# NextPro-v1.net
KiCad netlist of a schematic drawn in EAGLE
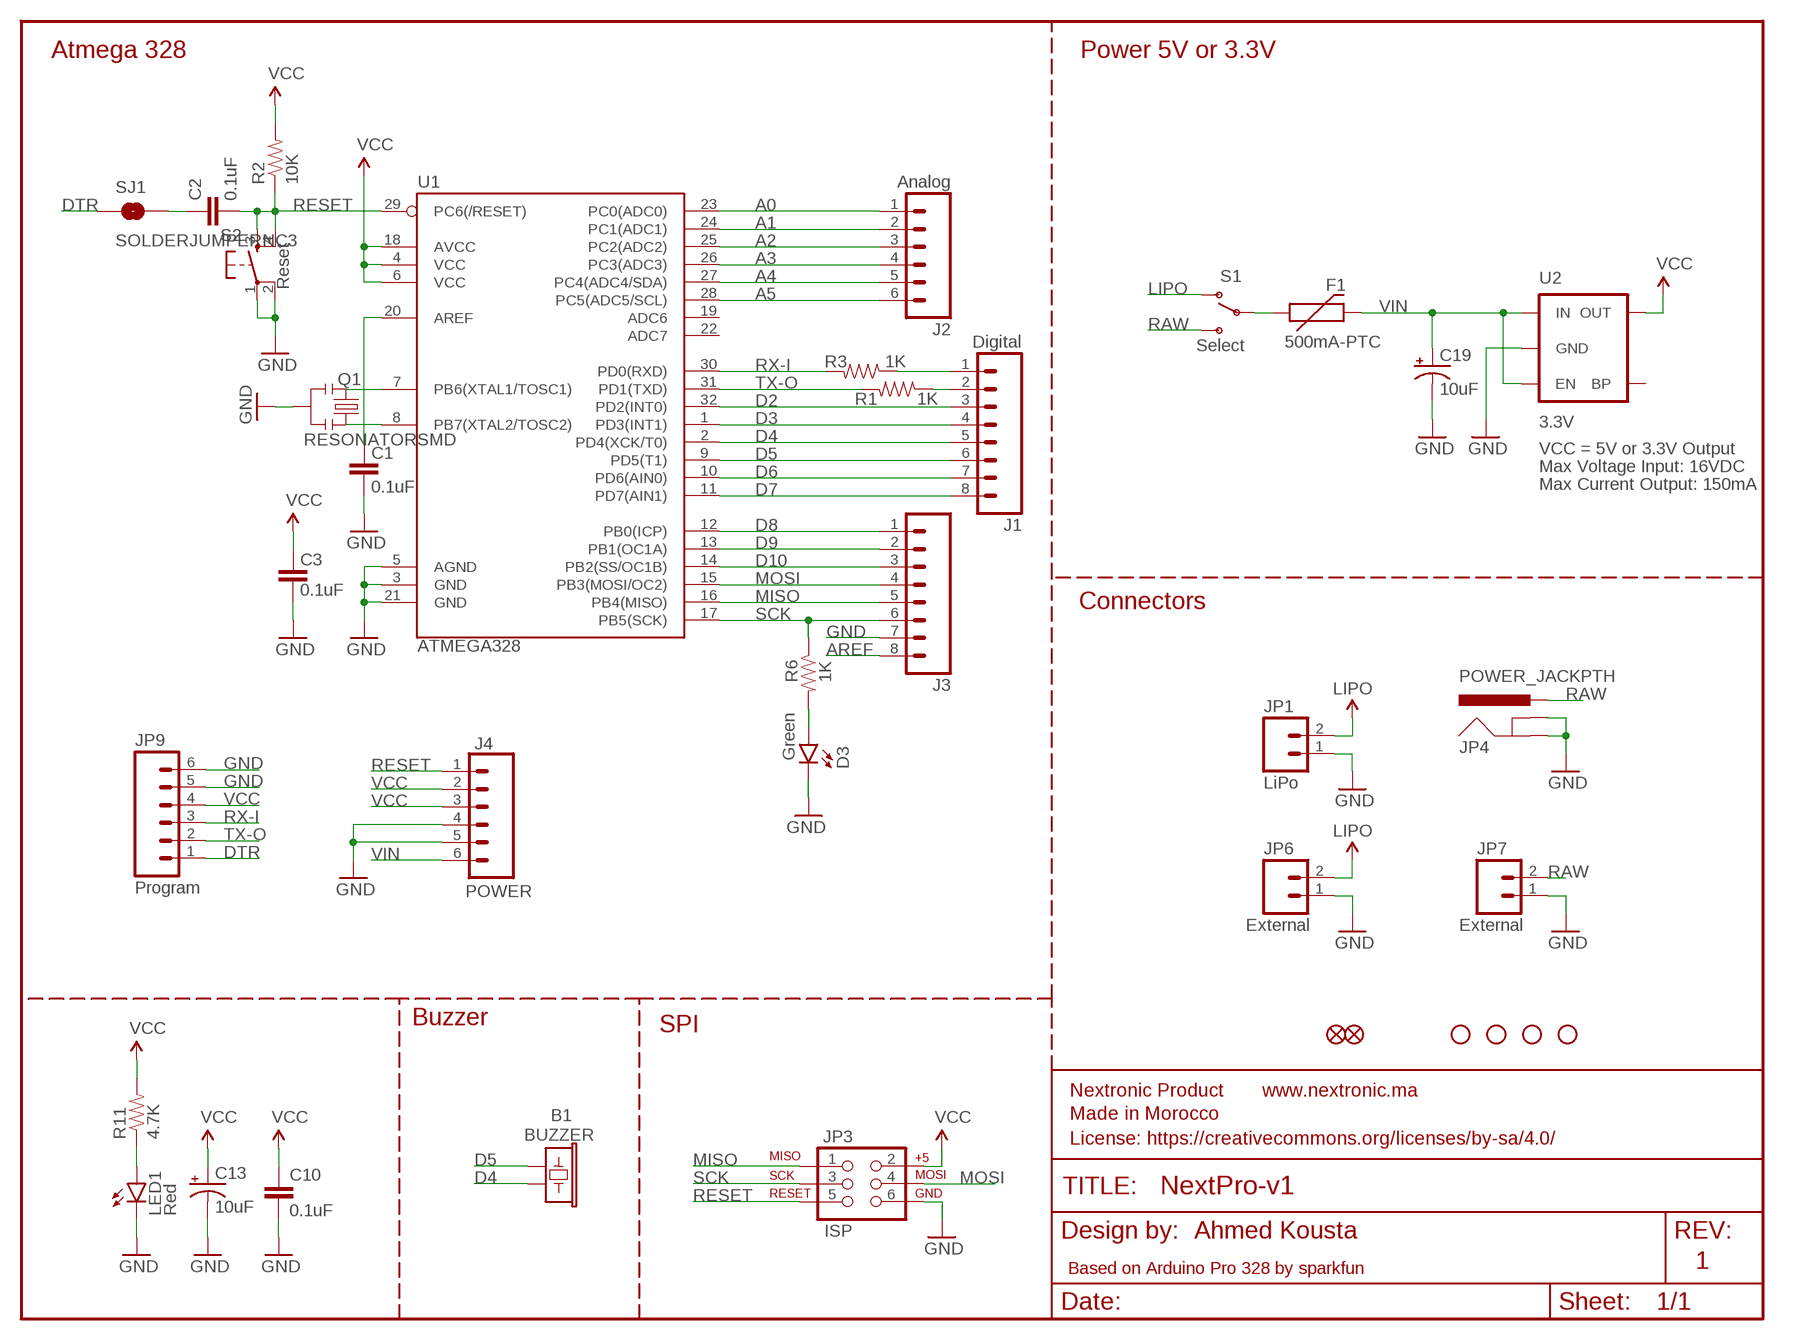
[diagram p0: schematic, sheet 1]

(export (version "E")
  (design (tool "Eeschema 10.0.6"))
  (components
    (comp (ref "B1")
      (value "BUZZER")
      (footprint "eagle-import:BUZZER-12MM")
      (libsource (lib "eagle-import") (part "BUZZERPTH"))
    )
    (comp (ref "C1")
      (value "0.1uF")
      (footprint "eagle-import:0603-CAP")
      (libsource (lib "eagle-import") (part "0.1UF-25V-5%(0603)"))
    )
    (comp (ref "C2")
      (value "0.1uF")
      (footprint "eagle-import:0603-CAP")
      (libsource (lib "eagle-import") (part "0.1UF-25V-5%(0603)"))
    )
    (comp (ref "C3")
      (value "0.1uF")
      (footprint "eagle-import:0603-CAP")
      (libsource (lib "eagle-import") (part "0.1UF-25V-5%(0603)"))
    )
    (comp (ref "C10")
      (value "0.1uF")
      (footprint "eagle-import:0603-CAP")
      (libsource (lib "eagle-import") (part "0.1UF-25V-5%(0603)"))
    )
    (comp (ref "C13")
      (value "10uF")
      (footprint "eagle-import:EIA3216")
      (libsource (lib "eagle-import") (part "CAP_POL1206"))
    )
    (comp (ref "C19")
      (value "10uF")
      (footprint "eagle-import:EIA3216")
      (libsource (lib "eagle-import") (part "CAP_POL1206"))
    )
    (comp (ref "D3")
      (value "Green")
      (footprint "eagle-import:LED-1206")
      (libsource (lib "eagle-import") (part "LED1206"))
    )
    (comp (ref "F1")
      (value "500mA-PTC")
      (footprint "eagle-import:PTC-1206")
      (libsource (lib "eagle-import") (part "PTCSMD"))
    )
    (comp (ref "FRAME1")
      (value "FRAME-LETTER")
      (footprint "eagle-import:CREATIVE_COMMONS")
      (libsource (lib "eagle-import") (part "FRAME-LETTER"))
    )
    (comp (ref "J1")
      (value "Digital")
      (footprint "eagle-import:1X08")
      (libsource (lib "eagle-import") (part "M081X08"))
    )
    (comp (ref "J2")
      (value "Analog")
      (footprint "eagle-import:1X06")
      (libsource (lib "eagle-import") (part "M06SIP"))
    )
    (comp (ref "J3")
      (value "M081X08")
      (footprint "eagle-import:1X08")
      (libsource (lib "eagle-import") (part "M081X08"))
    )
    (comp (ref "J4")
      (value "POWER")
      (footprint "eagle-import:1X06")
      (libsource (lib "eagle-import") (part "M06SIP"))
    )
    (comp (ref "JP1")
      (value "LiPo")
      (footprint "eagle-import:JST-2-PTH")
      (libsource (lib "eagle-import") (part "SparkFun-Connectors_M02JST-PTH-2"))
    )
    (comp (ref "JP2")
      (value "FIDUCIAL1X2.5")
      (footprint "eagle-import:FIDUCIAL-1X2.5")
      (libsource (lib "eagle-import") (part "FIDUCIAL1X2.5"))
    )
    (comp (ref "JP3")
      (value "ISP")
      (footprint "eagle-import:2X3")
      (libsource (lib "eagle-import") (part "AVR_SPI_PRG_6PTH"))
    )
    (comp (ref "JP4")
      (value "POWER_JACKPTH")
      (footprint "eagle-import:POWER_JACK_PTH")
      (libsource (lib "eagle-import") (part "POWER_JACKPTH"))
    )
    (comp (ref "JP5")
      (value "FIDUCIAL1X2.5")
      (footprint "eagle-import:FIDUCIAL-1X2.5")
      (libsource (lib "eagle-import") (part "FIDUCIAL1X2.5"))
    )
    (comp (ref "JP6")
      (value "External")
      (footprint "eagle-import:1X02")
      (libsource (lib "eagle-import") (part "M02PTH"))
    )
    (comp (ref "JP7")
      (value "External")
      (footprint "eagle-import:1X02_NO_SILK")
      (libsource (lib "eagle-import") (part "SparkFun-Connectors_M021X02_NO_SILK"))
    )
    (comp (ref "JP9")
      (value "Program")
      (footprint "eagle-import:1X06")
      (libsource (lib "eagle-import") (part "M06SILK_FEMALE_PTH"))
    )
    (comp (ref "LED1")
      (value "Red")
      (footprint "eagle-import:LED-1206")
      (libsource (lib "eagle-import") (part "LED1206"))
    )
    (comp (ref "Q1")
      (value "RESONATORSMD")
      (footprint "eagle-import:RESONATOR-SMD")
      (libsource (lib "eagle-import") (part "RESONATORSMD"))
    )
    (comp (ref "R1")
      (value "1K")
      (footprint "eagle-import:0603-RES")
      (libsource (lib "eagle-import") (part "1KOHM-1/10W-1%(0603)"))
    )
    (comp (ref "R2")
      (value "10K")
      (footprint "eagle-import:0603-RES")
      (libsource (lib "eagle-import") (part "1KOHM-1/10W-1%(0603)"))
    )
    (comp (ref "R3")
      (value "1K")
      (footprint "eagle-import:0603-RES")
      (libsource (lib "eagle-import") (part "1KOHM-1/10W-1%(0603)"))
    )
    (comp (ref "R6")
      (value "1K")
      (footprint "eagle-import:0603-RES")
      (libsource (lib "eagle-import") (part "1KOHM-1/10W-1%(0603)"))
    )
    (comp (ref "R11")
      (value "4.7K")
      (footprint "eagle-import:0603-RES")
      (libsource (lib "eagle-import") (part "1KOHM-1/10W-1%(0603)"))
    )
    (comp (ref "S1")
      (value "Select")
      (footprint "eagle-import:AYZ0202")
      (libsource (lib "eagle-import") (part "SWITCH-SPDTSMD"))
    )
    (comp (ref "S2")
      (value "Reset")
      (footprint "eagle-import:TACTILE-PTH")
      (libsource (lib "eagle-import") (part "TAC_SWITCHPTH"))
    )
    (comp (ref "SJ1")
      (value "SOLDERJUMPERNC3")
      (footprint "eagle-import:SJ_2S-NOTRACE")
      (libsource (lib "eagle-import") (part "SOLDERJUMPERNC2"))
    )
    (comp (ref "U$1")
      (value "STAND-OFF")
      (footprint "eagle-import:STAND-OFF")
      (libsource (lib "eagle-import") (part "STAND-OFF"))
    )
    (comp (ref "U$3")
      (value "STAND-OFF")
      (footprint "eagle-import:STAND-OFF")
      (libsource (lib "eagle-import") (part "STAND-OFF"))
    )
    (comp (ref "U$9")
      (value "STAND-OFF")
      (footprint "eagle-import:STAND-OFF")
      (libsource (lib "eagle-import") (part "STAND-OFF"))
    )
    (comp (ref "U$10")
      (value "STAND-OFF")
      (footprint "eagle-import:STAND-OFF")
      (libsource (lib "eagle-import") (part "STAND-OFF"))
    )
    (comp (ref "U1")
      (value "ATMEGA328")
      (footprint "eagle-import:TQFP32-08")
      (libsource (lib "eagle-import") (part "ATMEGA168"))
    )
    (comp (ref "U2")
      (value "3.3V")
      (footprint "eagle-import:SOT23-5")
      (libsource (lib "eagle-import") (part "V_REG_LDOSMD"))
    )
  )
  (nets
    (net (code "1") (name "/A0") (class "Default")
      (node (ref "J2") (pin "1") (pinfunction "1_1") (pintype "passive"))
      (node (ref "U1") (pin "23") (pinfunction "PC0(ADC0)_23") (pintype "bidirectional"))
    )
    (net (code "2") (name "/A1") (class "Default")
      (node (ref "J2") (pin "2") (pinfunction "2_2") (pintype "passive"))
      (node (ref "U1") (pin "24") (pinfunction "PC1(ADC1)_24") (pintype "bidirectional"))
    )
    (net (code "3") (name "/A2") (class "Default")
      (node (ref "J2") (pin "3") (pinfunction "3_3") (pintype "passive"))
      (node (ref "U1") (pin "25") (pinfunction "PC2(ADC2)_25") (pintype "bidirectional"))
    )
    (net (code "4") (name "/A3") (class "Default")
      (node (ref "J2") (pin "4") (pinfunction "4_4") (pintype "passive"))
      (node (ref "U1") (pin "26") (pinfunction "PC3(ADC3)_26") (pintype "bidirectional"))
    )
    (net (code "5") (name "/A4") (class "Default")
      (node (ref "J2") (pin "5") (pinfunction "5_5") (pintype "passive"))
      (node (ref "U1") (pin "27") (pinfunction "PC4(ADC4/SDA)_27") (pintype "bidirectional"))
    )
    (net (code "6") (name "/A5") (class "Default")
      (node (ref "J2") (pin "6") (pinfunction "6_6") (pintype "passive"))
      (node (ref "U1") (pin "28") (pinfunction "PC5(ADC5/SCL)_28") (pintype "bidirectional"))
    )
    (net (code "7") (name "/AREF") (class "Default")
      (node (ref "C1") (pin "2") (pinfunction "2_2") (pintype "passive"))
      (node (ref "J3") (pin "8") (pinfunction "8_8") (pintype "passive"))
      (node (ref "U1") (pin "20") (pinfunction "AREF_20") (pintype "bidirectional"))
    )
    (net (code "8") (name "/D2") (class "Default")
      (node (ref "J1") (pin "3") (pinfunction "3_3") (pintype "passive"))
      (node (ref "U1") (pin "32") (pinfunction "PD2(INT0)_32") (pintype "bidirectional"))
    )
    (net (code "9") (name "/D3") (class "Default")
      (node (ref "J1") (pin "4") (pinfunction "4_4") (pintype "passive"))
      (node (ref "U1") (pin "1") (pinfunction "PD3(INT1)_1") (pintype "bidirectional"))
    )
    (net (code "10") (name "/D4") (class "Default")
      (node (ref "B1") (pin "-") (pinfunction "2_-") (pintype "passive"))
      (node (ref "J1") (pin "5") (pinfunction "5_5") (pintype "passive"))
      (node (ref "U1") (pin "2") (pinfunction "PD4(XCK/T0)_2") (pintype "bidirectional"))
    )
    (net (code "11") (name "/D5") (class "Default")
      (node (ref "B1") (pin "+") (pinfunction "1_+") (pintype "passive"))
      (node (ref "J1") (pin "6") (pinfunction "6_6") (pintype "passive"))
      (node (ref "U1") (pin "9") (pinfunction "PD5(T1)_9") (pintype "bidirectional"))
    )
    (net (code "12") (name "/D6") (class "Default")
      (node (ref "J1") (pin "7") (pinfunction "7_7") (pintype "passive"))
      (node (ref "U1") (pin "10") (pinfunction "PD6(AIN0)_10") (pintype "bidirectional"))
    )
    (net (code "13") (name "/D7") (class "Default")
      (node (ref "J1") (pin "8") (pinfunction "8_8") (pintype "passive"))
      (node (ref "U1") (pin "11") (pinfunction "PD7(AIN1)_11") (pintype "bidirectional"))
    )
    (net (code "14") (name "/D8") (class "Default")
      (node (ref "J3") (pin "1") (pinfunction "1_1") (pintype "passive"))
      (node (ref "U1") (pin "12") (pinfunction "PB0(ICP)_12") (pintype "bidirectional"))
    )
    (net (code "15") (name "/D9") (class "Default")
      (node (ref "J3") (pin "2") (pinfunction "2_2") (pintype "passive"))
      (node (ref "U1") (pin "13") (pinfunction "PB1(OC1A)_13") (pintype "bidirectional"))
    )
    (net (code "16") (name "/D10") (class "Default")
      (node (ref "J3") (pin "3") (pinfunction "3_3") (pintype "passive"))
      (node (ref "U1") (pin "14") (pinfunction "PB2(SS/OC1B)_14") (pintype "bidirectional"))
    )
    (net (code "17") (name "/DTR") (class "Default")
      (node (ref "JP9") (pin "1") (pinfunction "1_1") (pintype "passive"))
      (node (ref "SJ1") (pin "1") (pinfunction "1_1") (pintype "passive"))
    )
    (net (code "18") (name "/MISO") (class "Default")
      (node (ref "J3") (pin "5") (pinfunction "5_5") (pintype "passive"))
      (node (ref "JP3") (pin "1") (pinfunction "1_1") (pintype "passive"))
      (node (ref "U1") (pin "16") (pinfunction "PB4(MISO)_16") (pintype "bidirectional"))
    )
    (net (code "19") (name "/MOSI") (class "Default")
      (node (ref "J3") (pin "4") (pinfunction "4_4") (pintype "passive"))
      (node (ref "JP3") (pin "4") (pinfunction "4_4") (pintype "passive"))
      (node (ref "U1") (pin "15") (pinfunction "PB3(MOSI/OC2)_15") (pintype "bidirectional"))
    )
    (net (code "20") (name "/RAW") (class "Default")
      (node (ref "JP4") (pin "PWR") (pinfunction "PWR_PWR") (pintype "bidirectional"))
      (node (ref "JP7") (pin "2") (pinfunction "2_2") (pintype "passive"))
      (node (ref "S1") (pin "3") (pinfunction "S_3") (pintype "passive"))
    )
    (net (code "21") (name "/RESET") (class "Default")
      (node (ref "C2") (pin "2") (pinfunction "2_2") (pintype "passive"))
      (node (ref "J4") (pin "1") (pinfunction "1_1") (pintype "passive"))
      (node (ref "JP3") (pin "5") (pinfunction "5_5") (pintype "passive"))
      (node (ref "R2") (pin "1") (pinfunction "1_1") (pintype "passive"))
      (node (ref "S2") (pin "3") (pinfunction "3_3") (pintype "passive"))
      (node (ref "S2") (pin "4") (pinfunction "4_4") (pintype "passive"))
      (node (ref "U1") (pin "29") (pinfunction "PC6(/RESET)_29") (pintype "bidirectional"))
    )
    (net (code "22") (name "/RX-I") (class "Default")
      (node (ref "JP9") (pin "3") (pinfunction "3_3") (pintype "passive"))
      (node (ref "R3") (pin "2") (pinfunction "2_2") (pintype "passive"))
      (node (ref "U1") (pin "30") (pinfunction "PD0(RXD)_30") (pintype "bidirectional"))
    )
    (net (code "23") (name "/SCK") (class "Default")
      (node (ref "J3") (pin "6") (pinfunction "6_6") (pintype "passive"))
      (node (ref "JP3") (pin "3") (pinfunction "3_3") (pintype "passive"))
      (node (ref "R6") (pin "1") (pinfunction "1_1") (pintype "passive"))
      (node (ref "U1") (pin "17") (pinfunction "PB5(SCK)_17") (pintype "bidirectional"))
    )
    (net (code "24") (name "/TX-O") (class "Default")
      (node (ref "JP9") (pin "2") (pinfunction "2_2") (pintype "passive"))
      (node (ref "R1") (pin "2") (pinfunction "2_2") (pintype "passive"))
      (node (ref "U1") (pin "31") (pinfunction "PD1(TXD)_31") (pintype "bidirectional"))
    )
    (net (code "25") (name "/VIN") (class "Default")
      (node (ref "C19") (pin "A") (pinfunction "+_A") (pintype "passive"))
      (node (ref "F1") (pin "2") (pinfunction "2_2") (pintype "bidirectional"))
      (node (ref "J4") (pin "6") (pinfunction "6_6") (pintype "passive"))
      (node (ref "U2") (pin "1") (pinfunction "IN_1") (pintype "input"))
      (node (ref "U2") (pin "3") (pinfunction "EN_3") (pintype "input"))
    )
    (net (code "26") (name "GND") (class "Default")
      (node (ref "C1") (pin "1") (pinfunction "1_1") (pintype "passive"))
      (node (ref "C10") (pin "2") (pinfunction "2_2") (pintype "passive"))
      (node (ref "C13") (pin "C") (pinfunction "-_C") (pintype "passive"))
      (node (ref "C19") (pin "C") (pinfunction "-_C") (pintype "passive"))
      (node (ref "C3") (pin "1") (pinfunction "1_1") (pintype "passive"))
      (node (ref "D3") (pin "C") (pinfunction "C_C") (pintype "passive"))
      (node (ref "J3") (pin "7") (pinfunction "7_7") (pintype "passive"))
      (node (ref "J4") (pin "4") (pinfunction "4_4") (pintype "passive"))
      (node (ref "J4") (pin "5") (pinfunction "5_5") (pintype "passive"))
      (node (ref "JP1") (pin "1") (pinfunction "1_1") (pintype "passive"))
      (node (ref "JP3") (pin "6") (pinfunction "6_6") (pintype "passive"))
      (node (ref "JP4") (pin "GND") (pinfunction "GND_GND") (pintype "bidirectional"))
      (node (ref "JP4") (pin "GNDBREAK") (pinfunction "GNDBREAK_GNDBREAK") (pintype "bidirectional"))
      (node (ref "JP6") (pin "1") (pinfunction "1_1") (pintype "passive"))
      (node (ref "JP7") (pin "1") (pinfunction "1_1") (pintype "passive"))
      (node (ref "JP9") (pin "5") (pinfunction "5_5") (pintype "passive"))
      (node (ref "JP9") (pin "6") (pinfunction "6_6") (pintype "passive"))
      (node (ref "LED1") (pin "C") (pinfunction "C_C") (pintype "passive"))
      (node (ref "Q1") (pin "2") (pinfunction "2_2") (pintype "passive"))
      (node (ref "S2") (pin "1") (pinfunction "1_1") (pintype "passive"))
      (node (ref "S2") (pin "2") (pinfunction "2_2") (pintype "passive"))
      (node (ref "U1") (pin "21") (pinfunction "GND_21") (pintype "bidirectional"))
      (node (ref "U1") (pin "3") (pinfunction "GND_3") (pintype "bidirectional"))
      (node (ref "U1") (pin "5") (pinfunction "AGND_5") (pintype "bidirectional"))
      (node (ref "U2") (pin "2") (pinfunction "GND_2") (pintype "input"))
    )
    (net (code "27") (name "LIPO") (class "Default")
      (node (ref "JP1") (pin "2") (pinfunction "2_2") (pintype "passive"))
      (node (ref "JP6") (pin "2") (pinfunction "2_2") (pintype "passive"))
      (node (ref "S1") (pin "1") (pinfunction "O_1") (pintype "passive"))
    )
    (net (code "28") (name "Net-(C2-Pad1)") (class "Default")
      (node (ref "C2") (pin "1") (pinfunction "1_1") (pintype "passive"))
      (node (ref "SJ1") (pin "2") (pinfunction "2_2") (pintype "passive"))
    )
    (net (code "29") (name "Net-(D3-PadA)") (class "Default")
      (node (ref "D3") (pin "A") (pinfunction "A_A") (pintype "passive"))
      (node (ref "R6") (pin "2") (pinfunction "2_2") (pintype "passive"))
    )
    (net (code "30") (name "Net-(J1-Pad1)") (class "Default")
      (node (ref "J1") (pin "1") (pinfunction "1_1") (pintype "passive"))
      (node (ref "R3") (pin "1") (pinfunction "1_1") (pintype "passive"))
    )
    (net (code "31") (name "Net-(J1-Pad2)") (class "Default")
      (node (ref "J1") (pin "2") (pinfunction "2_2") (pintype "passive"))
      (node (ref "R1") (pin "1") (pinfunction "1_1") (pintype "passive"))
    )
    (net (code "32") (name "Net-(LED1-PadA)") (class "Default")
      (node (ref "LED1") (pin "A") (pinfunction "A_A") (pintype "passive"))
      (node (ref "R11") (pin "1") (pinfunction "1_1") (pintype "passive"))
    )
    (net (code "33") (name "Net-(S1-P)") (class "Default")
      (node (ref "F1") (pin "1") (pinfunction "1_1") (pintype "bidirectional"))
      (node (ref "S1") (pin "2") (pinfunction "P_2") (pintype "passive"))
    )
    (net (code "34") (name "Net-(U1-PB6(XTAL1{slash}TOSC1))") (class "Default")
      (node (ref "Q1") (pin "3") (pinfunction "3_3") (pintype "passive"))
      (node (ref "U1") (pin "7") (pinfunction "PB6(XTAL1/TOSC1)_7") (pintype "bidirectional"))
    )
    (net (code "35") (name "Net-(U1-PB7(XTAL2{slash}TOSC2))") (class "Default")
      (node (ref "Q1") (pin "1") (pinfunction "1_1") (pintype "passive"))
      (node (ref "U1") (pin "8") (pinfunction "PB7(XTAL2/TOSC2)_8") (pintype "bidirectional"))
    )
    (net (code "36") (name "VCC") (class "Default")
      (node (ref "C10") (pin "1") (pinfunction "1_1") (pintype "passive"))
      (node (ref "C13") (pin "A") (pinfunction "+_A") (pintype "passive"))
      (node (ref "C3") (pin "2") (pinfunction "2_2") (pintype "passive"))
      (node (ref "J4") (pin "2") (pinfunction "2_2") (pintype "passive"))
      (node (ref "J4") (pin "3") (pinfunction "3_3") (pintype "passive"))
      (node (ref "JP3") (pin "2") (pinfunction "2_2") (pintype "passive"))
      (node (ref "JP9") (pin "4") (pinfunction "4_4") (pintype "passive"))
      (node (ref "R11") (pin "2") (pinfunction "2_2") (pintype "passive"))
      (node (ref "R2") (pin "2") (pinfunction "2_2") (pintype "passive"))
      (node (ref "U1") (pin "18") (pinfunction "AVCC_18") (pintype "bidirectional"))
      (node (ref "U1") (pin "4") (pinfunction "VCC_4") (pintype "bidirectional"))
      (node (ref "U1") (pin "6") (pinfunction "VCC_6") (pintype "bidirectional"))
      (node (ref "U2") (pin "5") (pinfunction "OUT_5") (pintype "passive"))
    )
    (net (code "37") (name "unconnected-(U1-ADC6-Pad19)") (class "Default")
      (node (ref "U1") (pin "19") (pinfunction "ADC6_19") (pintype "bidirectional"))
    )
    (net (code "38") (name "unconnected-(U1-ADC7-Pad22)") (class "Default")
      (node (ref "U1") (pin "22") (pinfunction "ADC7_22") (pintype "bidirectional"))
    )
    (net (code "39") (name "unconnected-(U2-BP-Pad4)") (class "Default")
      (node (ref "U2") (pin "4") (pinfunction "BP_4") (pintype "input"))
    )
  )
)
